# oktosema.net
KiCad netlist of a schematic drawn in EAGLE
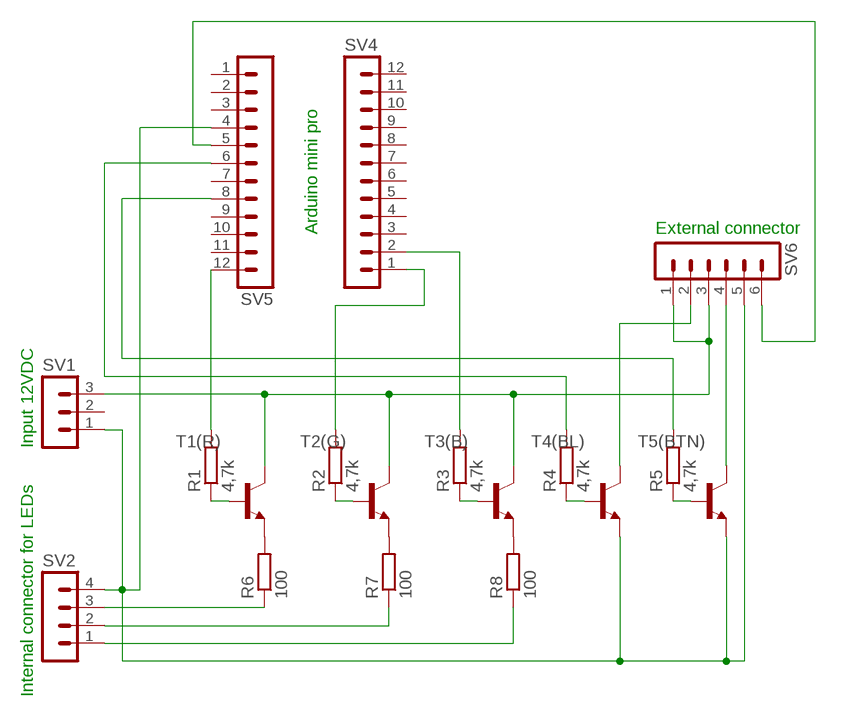
[diagram p0: schematic, sheet 1]

(export (version "E")
  (design (tool "Eeschema 10.0.6"))
  (components
    (comp (ref "R1")
      (value "4,7k")
      (footprint "eagle-import:0204_7")
      (libsource (lib "eagle-import") (part "R-EU_0204/7"))
    )
    (comp (ref "R2")
      (value "4,7k")
      (footprint "eagle-import:0204_7")
      (libsource (lib "eagle-import") (part "R-EU_0204/7"))
    )
    (comp (ref "R3")
      (value "4,7k")
      (footprint "eagle-import:0204_7")
      (libsource (lib "eagle-import") (part "R-EU_0204/7"))
    )
    (comp (ref "R4")
      (value "4,7k")
      (footprint "eagle-import:0204_7")
      (libsource (lib "eagle-import") (part "R-EU_0204/7"))
    )
    (comp (ref "R5")
      (value "4,7k")
      (footprint "eagle-import:0204_7")
      (libsource (lib "eagle-import") (part "R-EU_0204/7"))
    )
    (comp (ref "R6")
      (value "100")
      (footprint "eagle-import:0204_7")
      (libsource (lib "eagle-import") (part "R-EU_0204/7"))
    )
    (comp (ref "R7")
      (value "100")
      (footprint "eagle-import:0204_7")
      (libsource (lib "eagle-import") (part "R-EU_0204/7"))
    )
    (comp (ref "R8")
      (value "100")
      (footprint "eagle-import:0204_7")
      (libsource (lib "eagle-import") (part "R-EU_0204/7"))
    )
    (comp (ref "SV1")
      (value "MA03-1")
      (footprint "eagle-import:MA03-1")
      (libsource (lib "eagle-import") (part "MA03-1"))
    )
    (comp (ref "SV2")
      (value "MA04-1")
      (footprint "eagle-import:MA04-1")
      (libsource (lib "eagle-import") (part "MA04-1"))
    )
    (comp (ref "SV4")
      (value "MA12-1")
      (footprint "eagle-import:MA12-1")
      (libsource (lib "eagle-import") (part "MA12-1"))
    )
    (comp (ref "SV5")
      (value "MA12-1")
      (footprint "eagle-import:MA12-1")
      (libsource (lib "eagle-import") (part "MA12-1"))
    )
    (comp (ref "SV6")
      (value "MA06-1")
      (footprint "eagle-import:MA06-1")
      (libsource (lib "eagle-import") (part "MA06-1"))
    )
    (comp (ref "T1(R)")
      (value "BC337-25-NPN-TO92-CBE")
      (footprint "eagle-import:TO92-CBE")
      (libsource (lib "eagle-import") (part "-NPN-TO92-CBEBC337-25"))
    )
    (comp (ref "T2(G)")
      (value "BC337-25-NPN-TO92-CBE")
      (footprint "eagle-import:TO92-CBE")
      (libsource (lib "eagle-import") (part "-NPN-TO92-CBEBC337-25"))
    )
    (comp (ref "T3(B)")
      (value "BC337-25-NPN-TO92-CBE")
      (footprint "eagle-import:TO92-CBE")
      (libsource (lib "eagle-import") (part "-NPN-TO92-CBEBC337-25"))
    )
    (comp (ref "T4(BL)")
      (value "BC337-25-NPN-TO92-CBE")
      (footprint "eagle-import:TO92-CBE")
      (libsource (lib "eagle-import") (part "-NPN-TO92-CBEBC337-25"))
    )
    (comp (ref "T5(BTN)")
      (value "BC337-25-NPN-TO92-CBE")
      (footprint "eagle-import:TO92-CBE")
      (libsource (lib "eagle-import") (part "-NPN-TO92-CBEBC337-25"))
    )
  )
  (nets
    (net (code "1") (name "Net-(R1-Pad1)") (class "Default")
      (node (ref "R1") (pin "1") (pinfunction "1_1") (pintype "passive"))
      (node (ref "T1(R)") (pin "B") (pinfunction "B_B") (pintype "passive"))
    )
    (net (code "2") (name "Net-(R1-Pad2)") (class "Default")
      (node (ref "R1") (pin "2") (pinfunction "2_2") (pintype "passive"))
      (node (ref "SV5") (pin "12") (pinfunction "12_12") (pintype "passive"))
    )
    (net (code "3") (name "Net-(R2-Pad1)") (class "Default")
      (node (ref "R2") (pin "1") (pinfunction "1_1") (pintype "passive"))
      (node (ref "T2(G)") (pin "B") (pinfunction "B_B") (pintype "passive"))
    )
    (net (code "4") (name "Net-(R2-Pad2)") (class "Default")
      (node (ref "R2") (pin "2") (pinfunction "2_2") (pintype "passive"))
      (node (ref "SV4") (pin "1") (pinfunction "1_1") (pintype "passive"))
    )
    (net (code "5") (name "Net-(R3-Pad1)") (class "Default")
      (node (ref "R3") (pin "1") (pinfunction "1_1") (pintype "passive"))
      (node (ref "T3(B)") (pin "B") (pinfunction "B_B") (pintype "passive"))
    )
    (net (code "6") (name "Net-(R3-Pad2)") (class "Default")
      (node (ref "R3") (pin "2") (pinfunction "2_2") (pintype "passive"))
      (node (ref "SV4") (pin "2") (pinfunction "2_2") (pintype "passive"))
    )
    (net (code "7") (name "Net-(R4-Pad1)") (class "Default")
      (node (ref "R4") (pin "1") (pinfunction "1_1") (pintype "passive"))
      (node (ref "T4(BL)") (pin "B") (pinfunction "B_B") (pintype "passive"))
    )
    (net (code "8") (name "Net-(R4-Pad2)") (class "Default")
      (node (ref "R4") (pin "2") (pinfunction "2_2") (pintype "passive"))
      (node (ref "SV5") (pin "6") (pinfunction "6_6") (pintype "passive"))
    )
    (net (code "9") (name "Net-(R5-Pad1)") (class "Default")
      (node (ref "R5") (pin "1") (pinfunction "1_1") (pintype "passive"))
      (node (ref "T5(BTN)") (pin "B") (pinfunction "B_B") (pintype "passive"))
    )
    (net (code "10") (name "Net-(R5-Pad2)") (class "Default")
      (node (ref "R5") (pin "2") (pinfunction "2_2") (pintype "passive"))
      (node (ref "SV5") (pin "8") (pinfunction "8_8") (pintype "passive"))
    )
    (net (code "11") (name "Net-(R6-Pad1)") (class "Default")
      (node (ref "R6") (pin "1") (pinfunction "1_1") (pintype "passive"))
      (node (ref "SV2") (pin "3") (pinfunction "3_3") (pintype "passive"))
    )
    (net (code "12") (name "Net-(R6-Pad2)") (class "Default")
      (node (ref "R6") (pin "2") (pinfunction "2_2") (pintype "passive"))
      (node (ref "T1(R)") (pin "E") (pinfunction "E_E") (pintype "passive"))
    )
    (net (code "13") (name "Net-(R7-Pad1)") (class "Default")
      (node (ref "R7") (pin "1") (pinfunction "1_1") (pintype "passive"))
      (node (ref "SV2") (pin "2") (pinfunction "2_2") (pintype "passive"))
    )
    (net (code "14") (name "Net-(R7-Pad2)") (class "Default")
      (node (ref "R7") (pin "2") (pinfunction "2_2") (pintype "passive"))
      (node (ref "T2(G)") (pin "E") (pinfunction "E_E") (pintype "passive"))
    )
    (net (code "15") (name "Net-(R8-Pad1)") (class "Default")
      (node (ref "R8") (pin "1") (pinfunction "1_1") (pintype "passive"))
      (node (ref "SV2") (pin "1") (pinfunction "1_1") (pintype "passive"))
    )
    (net (code "16") (name "Net-(R8-Pad2)") (class "Default")
      (node (ref "R8") (pin "2") (pinfunction "2_2") (pintype "passive"))
      (node (ref "T3(B)") (pin "E") (pinfunction "E_E") (pintype "passive"))
    )
    (net (code "17") (name "Net-(SV1-Pad1)") (class "Default")
      (node (ref "SV1") (pin "1") (pinfunction "1_1") (pintype "passive"))
      (node (ref "SV2") (pin "4") (pinfunction "4_4") (pintype "passive"))
      (node (ref "SV5") (pin "4") (pinfunction "4_4") (pintype "passive"))
      (node (ref "SV6") (pin "5") (pinfunction "5_5") (pintype "passive"))
      (node (ref "T4(BL)") (pin "E") (pinfunction "E_E") (pintype "passive"))
      (node (ref "T5(BTN)") (pin "E") (pinfunction "E_E") (pintype "passive"))
    )
    (net (code "18") (name "Net-(SV1-Pad3)") (class "Default")
      (node (ref "SV1") (pin "3") (pinfunction "3_3") (pintype "passive"))
      (node (ref "SV6") (pin "1") (pinfunction "1_1") (pintype "passive"))
      (node (ref "SV6") (pin "3") (pinfunction "3_3") (pintype "passive"))
      (node (ref "T1(R)") (pin "C") (pinfunction "C_C") (pintype "passive"))
      (node (ref "T2(G)") (pin "C") (pinfunction "C_C") (pintype "passive"))
      (node (ref "T3(B)") (pin "C") (pinfunction "C_C") (pintype "passive"))
    )
    (net (code "19") (name "Net-(SV5-Pad5)") (class "Default")
      (node (ref "SV5") (pin "5") (pinfunction "5_5") (pintype "passive"))
      (node (ref "SV6") (pin "6") (pinfunction "6_6") (pintype "passive"))
    )
    (net (code "20") (name "Net-(SV6-Pad2)") (class "Default")
      (node (ref "SV6") (pin "2") (pinfunction "2_2") (pintype "passive"))
      (node (ref "T4(BL)") (pin "C") (pinfunction "C_C") (pintype "passive"))
    )
    (net (code "21") (name "Net-(SV6-Pad4)") (class "Default")
      (node (ref "SV6") (pin "4") (pinfunction "4_4") (pintype "passive"))
      (node (ref "T5(BTN)") (pin "C") (pinfunction "C_C") (pintype "passive"))
    )
    (net (code "22") (name "unconnected-(SV1-Pad2)") (class "Default")
      (node (ref "SV1") (pin "2") (pinfunction "2_2") (pintype "passive"))
    )
    (net (code "23") (name "unconnected-(SV4-Pad3)") (class "Default")
      (node (ref "SV4") (pin "3") (pinfunction "3_3") (pintype "passive"))
    )
    (net (code "24") (name "unconnected-(SV4-Pad4)") (class "Default")
      (node (ref "SV4") (pin "4") (pinfunction "4_4") (pintype "passive"))
    )
    (net (code "25") (name "unconnected-(SV4-Pad5)") (class "Default")
      (node (ref "SV4") (pin "5") (pinfunction "5_5") (pintype "passive"))
    )
    (net (code "26") (name "unconnected-(SV4-Pad6)") (class "Default")
      (node (ref "SV4") (pin "6") (pinfunction "6_6") (pintype "passive"))
    )
    (net (code "27") (name "unconnected-(SV4-Pad7)") (class "Default")
      (node (ref "SV4") (pin "7") (pinfunction "7_7") (pintype "passive"))
    )
    (net (code "28") (name "unconnected-(SV4-Pad8)") (class "Default")
      (node (ref "SV4") (pin "8") (pinfunction "8_8") (pintype "passive"))
    )
    (net (code "29") (name "unconnected-(SV4-Pad9)") (class "Default")
      (node (ref "SV4") (pin "9") (pinfunction "9_9") (pintype "passive"))
    )
    (net (code "30") (name "unconnected-(SV4-Pad10)") (class "Default")
      (node (ref "SV4") (pin "10") (pinfunction "10_10") (pintype "passive"))
    )
    (net (code "31") (name "unconnected-(SV4-Pad11)") (class "Default")
      (node (ref "SV4") (pin "11") (pinfunction "11_11") (pintype "passive"))
    )
    (net (code "32") (name "unconnected-(SV4-Pad12)") (class "Default")
      (node (ref "SV4") (pin "12") (pinfunction "12_12") (pintype "passive"))
    )
    (net (code "33") (name "unconnected-(SV5-Pad1)") (class "Default")
      (node (ref "SV5") (pin "1") (pinfunction "1_1") (pintype "passive"))
    )
    (net (code "34") (name "unconnected-(SV5-Pad2)") (class "Default")
      (node (ref "SV5") (pin "2") (pinfunction "2_2") (pintype "passive"))
    )
    (net (code "35") (name "unconnected-(SV5-Pad3)") (class "Default")
      (node (ref "SV5") (pin "3") (pinfunction "3_3") (pintype "passive"))
    )
    (net (code "36") (name "unconnected-(SV5-Pad7)") (class "Default")
      (node (ref "SV5") (pin "7") (pinfunction "7_7") (pintype "passive"))
    )
    (net (code "37") (name "unconnected-(SV5-Pad9)") (class "Default")
      (node (ref "SV5") (pin "9") (pinfunction "9_9") (pintype "passive"))
    )
    (net (code "38") (name "unconnected-(SV5-Pad10)") (class "Default")
      (node (ref "SV5") (pin "10") (pinfunction "10_10") (pintype "passive"))
    )
    (net (code "39") (name "unconnected-(SV5-Pad11)") (class "Default")
      (node (ref "SV5") (pin "11") (pinfunction "11_11") (pintype "passive"))
    )
  )
)
